# ICL7660.net
KiCad netlist of a schematic drawn in EAGLE
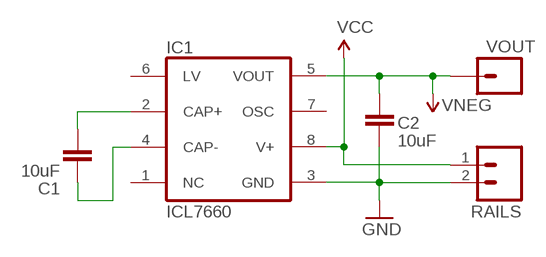
[diagram p0: schematic, sheet 1]

(export (version "E")
  (design (tool "Eeschema 10.0.6"))
  (components
    (comp (ref "C1")
      (value "10uF")
      (footprint "eagle-import:C1206")
      (libsource (lib "eagle-import") (part "CAPACITOR_NPOL-1206"))
    )
    (comp (ref "C2")
      (value "10uF")
      (footprint "eagle-import:C1206")
      (libsource (lib "eagle-import") (part "CAPACITOR_NPOL-1206"))
    )
    (comp (ref "IC1")
      (value "ICL7660")
      (footprint "eagle-import:SO08")
      (fields (field (name "MF") "MAXIM") (field (name "MPN") "ICL7660CSA"))
      (libsource (lib "eagle-import") (part "ICL7660CSA"))
    )
    (comp (ref "RAILS")
      (value "M02PTH")
      (footprint "eagle-import:1X02")
      (libsource (lib "eagle-import") (part "M02PTH"))
    )
    (comp (ref "VOUT")
      (value "M01PTH")
      (footprint "eagle-import:1X01")
      (libsource (lib "eagle-import") (part "M01PTH"))
    )
  )
  (nets
    (net (code "1") (name "GND") (class "Default")
      (node (ref "C2") (pin "2") (pinfunction "2_2") (pintype "passive"))
      (node (ref "IC1") (pin "3") (pinfunction "GND_3") (pintype "power_in"))
      (node (ref "RAILS") (pin "2") (pinfunction "2_2") (pintype "passive"))
    )
    (net (code "2") (name "Net-(IC1-CAP+)") (class "Default")
      (node (ref "C1") (pin "2") (pinfunction "2_2") (pintype "passive"))
      (node (ref "IC1") (pin "2") (pinfunction "CAP+_2") (pintype "passive"))
    )
    (net (code "3") (name "Net-(IC1-CAP-)") (class "Default")
      (node (ref "C1") (pin "1") (pinfunction "1_1") (pintype "passive"))
      (node (ref "IC1") (pin "4") (pinfunction "CAP-_4") (pintype "passive"))
    )
    (net (code "4") (name "VCC") (class "Default")
      (node (ref "IC1") (pin "8") (pinfunction "V+_8") (pintype "power_in"))
      (node (ref "RAILS") (pin "1") (pinfunction "1_1") (pintype "passive"))
    )
    (net (code "5") (name "VNEG") (class "Default")
      (node (ref "C2") (pin "1") (pinfunction "1_1") (pintype "passive"))
      (node (ref "IC1") (pin "5") (pinfunction "VOUT_5") (pintype "output"))
      (node (ref "VOUT") (pin "1") (pinfunction "1_1") (pintype "passive"))
    )
    (net (code "6") (name "unconnected-(IC1-LV-Pad6)") (class "Default")
      (node (ref "IC1") (pin "6") (pinfunction "LV_6") (pintype "passive"))
    )
    (net (code "7") (name "unconnected-(IC1-NC-Pad1)") (class "Default")
      (node (ref "IC1") (pin "1") (pinfunction "NC_1") (pintype "no_connect"))
    )
    (net (code "8") (name "unconnected-(IC1-OSC-Pad7)") (class "Default")
      (node (ref "IC1") (pin "7") (pinfunction "OSC_7") (pintype "output"))
    )
  )
)
